# Sheet1.net
KiCad netlist of a schematic drawn in Altium Designer
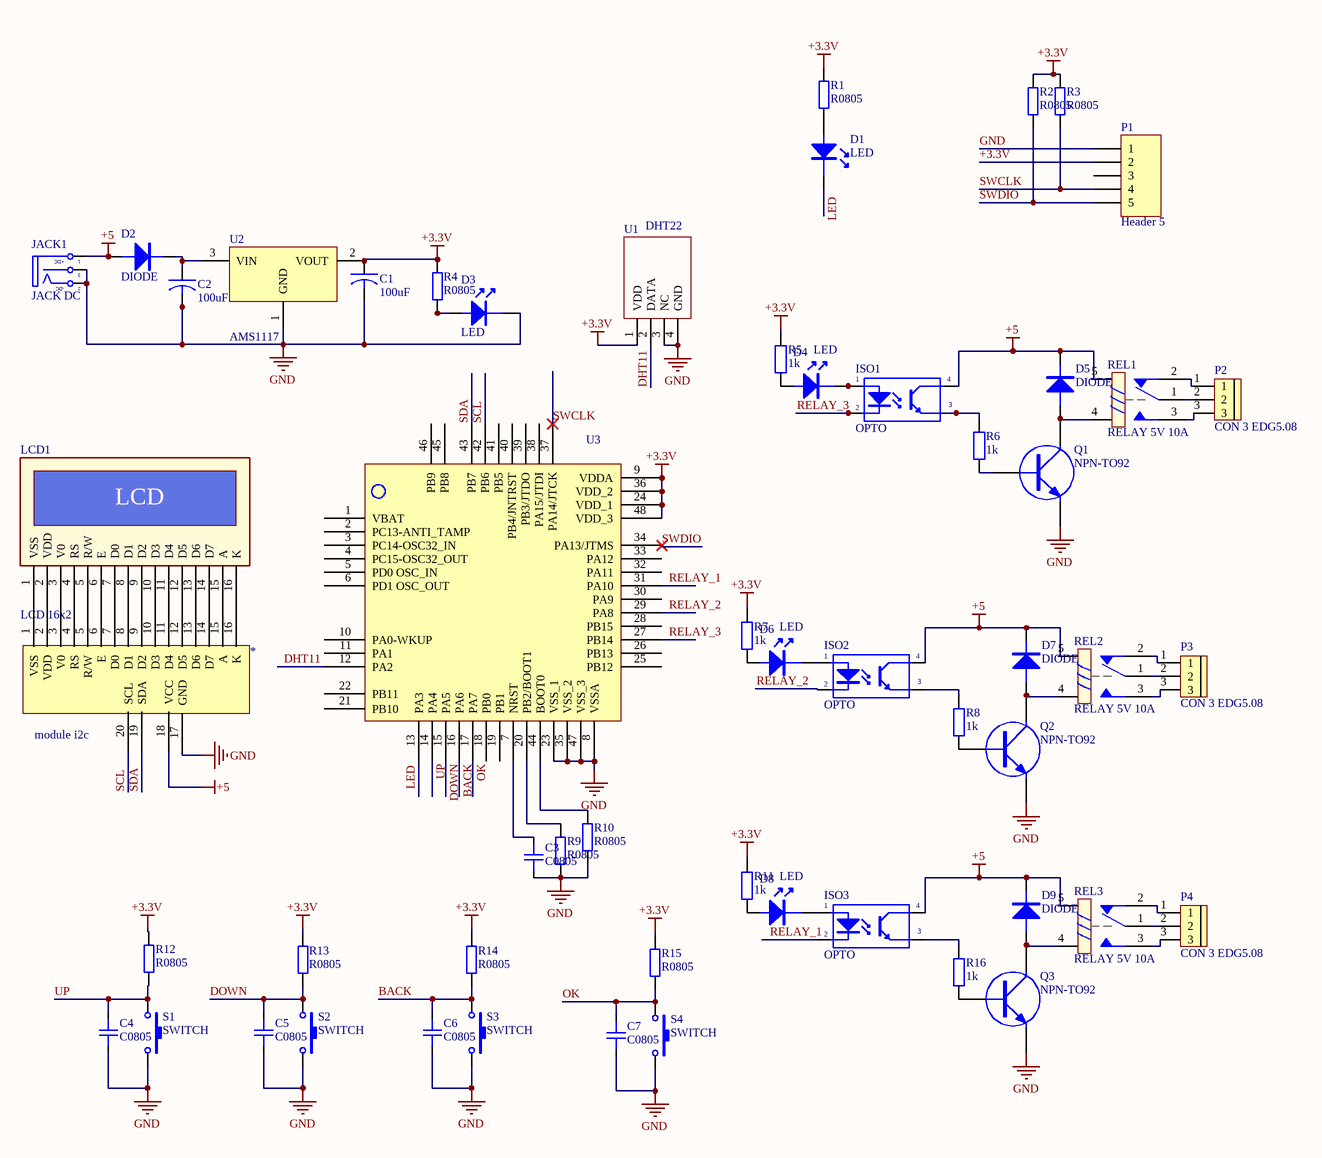
[diagram p0: Sheet1.SchDoc]

(export (version "E")
  (design (tool "Eeschema 10.0.6"))
  (components
    (comp (ref "*")
      (value "module i2c")
      (footprint "module_i2c")
      (libsource (lib "bethu") (part "module i2c"))
    )
    (comp (ref "C1") (value "100uF") (footprint "CAP_0805") (libsource (lib "bethu") (part "CAPACITOR")))
    (comp (ref "C2") (value "100uF") (footprint "CAP_0805") (libsource (lib "bethu") (part "CAPACITOR")))
    (comp (ref "C3")
      (value "C0805")
      (footprint "CAP_0805")
      (description "Capacitor SMD 0805")
      (libsource (lib "bethu") (part "CAP_0805"))
    )
    (comp (ref "C4")
      (value "C0805")
      (footprint "CAP_0805")
      (description "Capacitor SMD 0805")
      (libsource (lib "bethu") (part "CAP_0805"))
    )
    (comp (ref "C5")
      (value "C0805")
      (footprint "CAP_0805")
      (description "Capacitor SMD 0805")
      (libsource (lib "bethu") (part "CAP_0805"))
    )
    (comp (ref "C6")
      (value "C0805")
      (footprint "CAP_0805")
      (description "Capacitor SMD 0805")
      (libsource (lib "bethu") (part "CAP_0805"))
    )
    (comp (ref "C7")
      (value "C0805")
      (footprint "CAP_0805")
      (description "Capacitor SMD 0805")
      (libsource (lib "bethu") (part "CAP_0805"))
    )
    (comp (ref "D1") (value "LED") (footprint "LED5MM RED") (libsource (lib "bethu") (part "LED")))
    (comp (ref "D2") (value "DIODE") (footprint "DIODE SMA") (libsource (lib "bethu") (part "DIODE")))
    (comp (ref "D3") (value "LED") (footprint "LED5MM RED") (libsource (lib "bethu") (part "LED")))
    (comp (ref "D4") (value "LED") (footprint "LED5MM RED") (libsource (lib "bethu") (part "LED")))
    (comp (ref "D5") (value "DIODE") (footprint "DIODE DIP") (libsource (lib "bethu") (part "DIODE")))
    (comp (ref "D6") (value "LED") (footprint "LED5MM RED") (libsource (lib "bethu") (part "LED")))
    (comp (ref "D7") (value "DIODE") (footprint "DIODE DIP") (libsource (lib "bethu") (part "DIODE")))
    (comp (ref "D8") (value "LED") (footprint "LED5MM RED") (libsource (lib "bethu") (part "LED")))
    (comp (ref "D9") (value "DIODE") (footprint "DIODE DIP") (libsource (lib "bethu") (part "DIODE")))
    (comp (ref "ISO1") (value "OPTO") (footprint "PC817 DIP") (libsource (lib "bethu") (part "OPTO")))
    (comp (ref "ISO2") (value "OPTO") (footprint "PC817 DIP") (libsource (lib "bethu") (part "OPTO")))
    (comp (ref "ISO3") (value "OPTO") (footprint "PC817 DIP") (libsource (lib "bethu") (part "OPTO")))
    (comp (ref "JACK1") (value "JACK DC") (footprint "JACK DC") (libsource (lib "bethu") (part "JACK DC")))
    (comp (ref "LCD1")
      (value "LCD 16x2")
      (footprint "LCD 16x2-A")
      (libsource (lib "bethu") (part "LCD 16x2"))
    )
    (comp (ref "P1")
      (value "Header 5")
      (footprint "JP 1X5 DT")
      (fields (field (name "PUBLISHER") "Altium Limited"))
      (libsource (lib "bethu") (part "Header 5"))
    )
    (comp (ref "P2")
      (value "CON 3 EDG5.08")
      (footprint "Con 3 KF301 5.08")
      (description "Cắm")
      (libsource (lib "bethu") (part "CON 3 EDG5.08"))
    )
    (comp (ref "P3")
      (value "CON 3 EDG5.08")
      (footprint "Con 3 KF301 5.08")
      (description "Cắm")
      (libsource (lib "bethu") (part "CON 3 EDG5.08"))
    )
    (comp (ref "P4")
      (value "CON 3 EDG5.08")
      (footprint "Con 3 KF301 5.08")
      (description "Cắm")
      (libsource (lib "bethu") (part "CON 3 EDG5.08"))
    )
    (comp (ref "Q1") (value "NPN-TO92") (footprint "TO-92") (libsource (lib "bethu") (part "NPN-TO92")))
    (comp (ref "Q2") (value "NPN-TO92") (footprint "TO-92") (libsource (lib "bethu") (part "NPN-TO92")))
    (comp (ref "Q3") (value "NPN-TO92") (footprint "TO-92") (libsource (lib "bethu") (part "NPN-TO92")))
    (comp (ref "R1")
      (value "R0805")
      (footprint "RES_0805")
      (description "Resistor SMD 0805")
      (libsource (lib "bethu") (part "RES_0805"))
    )
    (comp (ref "R2")
      (value "R0805")
      (footprint "RES_0805")
      (description "Resistor SMD 0805")
      (libsource (lib "bethu") (part "RES_0805"))
    )
    (comp (ref "R3")
      (value "R0805")
      (footprint "RES_0805")
      (description "Resistor SMD 0805")
      (libsource (lib "bethu") (part "RES_0805"))
    )
    (comp (ref "R4")
      (value "R0805")
      (footprint "RES_0805")
      (description "Resistor SMD 0805")
      (libsource (lib "bethu") (part "RES_0805"))
    )
    (comp (ref "R5") (value "1k") (footprint "RESISTOR") (libsource (lib "bethu") (part "RESISTOR")))
    (comp (ref "R6") (value "1k") (footprint "RESISTOR") (libsource (lib "bethu") (part "RESISTOR")))
    (comp (ref "R7") (value "1k") (footprint "RESISTOR") (libsource (lib "bethu") (part "RESISTOR")))
    (comp (ref "R8") (value "1k") (footprint "RESISTOR") (libsource (lib "bethu") (part "RESISTOR")))
    (comp (ref "R9")
      (value "R0805")
      (footprint "RES_0805")
      (description "Resistor SMD 0805")
      (libsource (lib "bethu") (part "RES_0805"))
    )
    (comp (ref "R10")
      (value "R0805")
      (footprint "RES_0805")
      (description "Resistor SMD 0805")
      (libsource (lib "bethu") (part "RES_0805"))
    )
    (comp (ref "R11") (value "1k") (footprint "RESISTOR") (libsource (lib "bethu") (part "RESISTOR")))
    (comp (ref "R12")
      (value "R0805")
      (footprint "RES_0805")
      (description "Resistor SMD 0805")
      (libsource (lib "bethu") (part "RES_0805"))
    )
    (comp (ref "R13")
      (value "R0805")
      (footprint "RES_0805")
      (description "Resistor SMD 0805")
      (libsource (lib "bethu") (part "RES_0805"))
    )
    (comp (ref "R14")
      (value "R0805")
      (footprint "RES_0805")
      (description "Resistor SMD 0805")
      (libsource (lib "bethu") (part "RES_0805"))
    )
    (comp (ref "R15")
      (value "R0805")
      (footprint "RES_0805")
      (description "Resistor SMD 0805")
      (libsource (lib "bethu") (part "RES_0805"))
    )
    (comp (ref "R16") (value "1k") (footprint "RESISTOR") (libsource (lib "bethu") (part "RESISTOR")))
    (comp (ref "REL1")
      (value "RELAY 5V 10A")
      (footprint "RELAY 5V-10A")
      (libsource (lib "bethu") (part "RELAY 5V 10A"))
    )
    (comp (ref "REL2")
      (value "RELAY 5V 10A")
      (footprint "RELAY 5V-10A")
      (libsource (lib "bethu") (part "RELAY 5V 10A"))
    )
    (comp (ref "REL3")
      (value "RELAY 5V 10A")
      (footprint "RELAY 5V-10A")
      (libsource (lib "bethu") (part "RELAY 5V 10A"))
    )
    (comp (ref "S1")
      (value "SWITCH")
      (footprint "SW 4PIN 12x12x7")
      (fields (field (name "PUBLISHER") "Altium Limited"))
      (libsource (lib "bethu") (part "SWITCH"))
    )
    (comp (ref "S2")
      (value "SWITCH")
      (footprint "SW 4PIN 12x12x7")
      (fields (field (name "PUBLISHER") "Altium Limited"))
      (libsource (lib "bethu") (part "SWITCH"))
    )
    (comp (ref "S3")
      (value "SWITCH")
      (footprint "SW 4PIN 12x12x7")
      (fields (field (name "PUBLISHER") "Altium Limited"))
      (libsource (lib "bethu") (part "SWITCH"))
    )
    (comp (ref "S4")
      (value "SWITCH")
      (footprint "SW 4PIN 12x12x7")
      (fields (field (name "PUBLISHER") "Altium Limited"))
      (libsource (lib "bethu") (part "SWITCH"))
    )
    (comp (ref "U1") (value "DHT22") (footprint "DHT22") (libsource (lib "bethu") (part "DHT22")))
    (comp (ref "U2")
      (value "AMS1117")
      (footprint "SOT223 - 3 LEAD")
      (libsource (lib "bethu") (part "AMS1117"))
    )
    (comp (ref "U3")
      (value "STM32F103C8T6-LQFP48")
      (footprint "LQFP 48 PIN")
      (fields (field (name "PUBLISHER") "Altium Limited"))
      (libsource (lib "bethu") (part "STM32F103C8T6-LQFP48"))
    )
  )
  (nets
    (net (code "1") (name "+3.3V") (class "Default")
      (node (ref "C1") (pin "1") (pinfunction "1_1") (pintype "passive"))
      (node (ref "P1") (pin "2") (pinfunction "2_2") (pintype "passive"))
      (node (ref "R1") (pin "1") (pinfunction "1_1") (pintype "passive"))
      (node (ref "R11") (pin "2") (pinfunction "2_2") (pintype "passive"))
      (node (ref "R12") (pin "2") (pinfunction "2_2") (pintype "passive"))
      (node (ref "R13") (pin "2") (pinfunction "2_2") (pintype "passive"))
      (node (ref "R14") (pin "2") (pinfunction "2_2") (pintype "passive"))
      (node (ref "R15") (pin "2") (pinfunction "2_2") (pintype "passive"))
      (node (ref "R2") (pin "1") (pinfunction "1_1") (pintype "passive"))
      (node (ref "R3") (pin "1") (pinfunction "1_1") (pintype "passive"))
      (node (ref "R4") (pin "1") (pinfunction "1_1") (pintype "passive"))
      (node (ref "R5") (pin "2") (pinfunction "2_2") (pintype "passive"))
      (node (ref "R7") (pin "2") (pinfunction "2_2") (pintype "passive"))
      (node (ref "U1") (pin "1") (pinfunction "VDD_1") (pintype "passive"))
      (node (ref "U2") (pin "2") (pinfunction "VOUT_2") (pintype "passive"))
      (node (ref "U3") (pin "24") (pinfunction "VDD_1_24") (pintype "passive"))
      (node (ref "U3") (pin "36") (pinfunction "VDD_2_36") (pintype "passive"))
      (node (ref "U3") (pin "48") (pinfunction "VDD_3_48") (pintype "passive"))
      (node (ref "U3") (pin "9") (pinfunction "VDDA_9") (pintype "passive"))
    )
    (net (code "2") (name "+5") (class "Default")
      (node (ref "*") (pin "18") (pinfunction "VCC_18") (pintype "passive"))
      (node (ref "D2") (pin "1") (pinfunction "1_1") (pintype "passive"))
      (node (ref "D5") (pin "2") (pinfunction "2_2") (pintype "passive"))
      (node (ref "D7") (pin "2") (pinfunction "2_2") (pintype "passive"))
      (node (ref "D9") (pin "2") (pinfunction "2_2") (pintype "passive"))
      (node (ref "ISO1") (pin "4") (pinfunction "C_4") (pintype "passive"))
      (node (ref "ISO2") (pin "4") (pinfunction "C_4") (pintype "passive"))
      (node (ref "ISO3") (pin "4") (pinfunction "C_4") (pintype "passive"))
      (node (ref "JACK1") (pin "1") (pinfunction "T_1") (pintype "passive"))
      (node (ref "REL1") (pin "5") (pinfunction "5_5") (pintype "passive"))
      (node (ref "REL2") (pin "5") (pinfunction "5_5") (pintype "passive"))
      (node (ref "REL3") (pin "5") (pinfunction "5_5") (pintype "passive"))
    )
    (net (code "3") (name "/BACK") (class "Default")
      (node (ref "C6") (pin "1") (pinfunction "1_1") (pintype "passive"))
      (node (ref "R14") (pin "1") (pinfunction "1_1") (pintype "passive"))
      (node (ref "S3") (pin "1") (pinfunction "1_1") (pintype "passive"))
      (node (ref "U3") (pin "16") (pinfunction "PA6_16") (pintype "passive"))
    )
    (net (code "4") (name "/DHT11") (class "Default")
      (node (ref "U1") (pin "2") (pinfunction "DATA_2") (pintype "passive"))
      (node (ref "U3") (pin "12") (pinfunction "PA2_12") (pintype "passive"))
    )
    (net (code "5") (name "/DOWN") (class "Default")
      (node (ref "C5") (pin "1") (pinfunction "1_1") (pintype "passive"))
      (node (ref "R13") (pin "1") (pinfunction "1_1") (pintype "passive"))
      (node (ref "S2") (pin "1") (pinfunction "1_1") (pintype "passive"))
      (node (ref "U3") (pin "15") (pinfunction "PA5_15") (pintype "passive"))
    )
    (net (code "6") (name "/LED") (class "Default")
      (node (ref "D1") (pin "2") (pinfunction "2_2") (pintype "passive"))
      (node (ref "U3") (pin "13") (pinfunction "PA3_13") (pintype "passive"))
    )
    (net (code "7") (name "/OK") (class "Default")
      (node (ref "C7") (pin "1") (pinfunction "1_1") (pintype "passive"))
      (node (ref "R15") (pin "1") (pinfunction "1_1") (pintype "passive"))
      (node (ref "S4") (pin "1") (pinfunction "1_1") (pintype "passive"))
      (node (ref "U3") (pin "17") (pinfunction "PA7_17") (pintype "passive"))
    )
    (net (code "8") (name "/RELAY_1") (class "Default")
      (node (ref "ISO3") (pin "2") (pinfunction "K_2") (pintype "passive"))
      (node (ref "U3") (pin "31") (pinfunction "PA10_31") (pintype "passive"))
    )
    (net (code "9") (name "/RELAY_2") (class "Default")
      (node (ref "ISO2") (pin "2") (pinfunction "K_2") (pintype "passive"))
      (node (ref "U3") (pin "29") (pinfunction "PA8_29") (pintype "passive"))
    )
    (net (code "10") (name "/RELAY_3") (class "Default")
      (node (ref "ISO1") (pin "2") (pinfunction "K_2") (pintype "passive"))
      (node (ref "U3") (pin "27") (pinfunction "PB14_27") (pintype "passive"))
    )
    (net (code "11") (name "/SCL") (class "Default")
      (node (ref "*") (pin "20") (pinfunction "SCL_20") (pintype "passive"))
      (node (ref "U3") (pin "42") (pinfunction "PB6_42") (pintype "passive"))
    )
    (net (code "12") (name "/SDA") (class "Default")
      (node (ref "*") (pin "19") (pinfunction "SDA_19") (pintype "passive"))
      (node (ref "U3") (pin "43") (pinfunction "PB7_43") (pintype "passive"))
    )
    (net (code "13") (name "/SWCLK") (class "Default")
      (node (ref "P1") (pin "4") (pinfunction "4_4") (pintype "passive"))
      (node (ref "R3") (pin "2") (pinfunction "2_2") (pintype "passive"))
      (node (ref "U3") (pin "37") (pinfunction "PA14/JTCK_37") (pintype "passive"))
    )
    (net (code "14") (name "/SWDIO") (class "Default")
      (node (ref "P1") (pin "5") (pinfunction "5_5") (pintype "passive"))
      (node (ref "R2") (pin "2") (pinfunction "2_2") (pintype "passive"))
      (node (ref "U3") (pin "34") (pinfunction "PA13/JTMS_34") (pintype "passive"))
    )
    (net (code "15") (name "/UP") (class "Default")
      (node (ref "C4") (pin "1") (pinfunction "1_1") (pintype "passive"))
      (node (ref "R12") (pin "1") (pinfunction "1_1") (pintype "passive"))
      (node (ref "S1") (pin "1") (pinfunction "1_1") (pintype "passive"))
      (node (ref "U3") (pin "14") (pinfunction "PA4_14") (pintype "passive"))
    )
    (net (code "16") (name "GND") (class "Default")
      (node (ref "*") (pin "17") (pinfunction "GND_17") (pintype "passive"))
      (node (ref "C1") (pin "2") (pinfunction "2_2") (pintype "passive"))
      (node (ref "C2") (pin "2") (pinfunction "2_2") (pintype "passive"))
      (node (ref "C3") (pin "1") (pinfunction "1_1") (pintype "passive"))
      (node (ref "C4") (pin "2") (pinfunction "2_2") (pintype "passive"))
      (node (ref "C5") (pin "2") (pinfunction "2_2") (pintype "passive"))
      (node (ref "C6") (pin "2") (pinfunction "2_2") (pintype "passive"))
      (node (ref "C7") (pin "2") (pinfunction "2_2") (pintype "passive"))
      (node (ref "D3") (pin "2") (pinfunction "2_2") (pintype "passive"))
      (node (ref "JACK1") (pin "2") (pinfunction "TN_2") (pintype "passive"))
      (node (ref "JACK1") (pin "3") (pinfunction "S_3") (pintype "power_in"))
      (node (ref "P1") (pin "1") (pinfunction "1_1") (pintype "passive"))
      (node (ref "Q1") (pin "1") (pinfunction "E_1") (pintype "passive"))
      (node (ref "Q2") (pin "1") (pinfunction "E_1") (pintype "passive"))
      (node (ref "Q3") (pin "1") (pinfunction "E_1") (pintype "passive"))
      (node (ref "R10") (pin "1") (pinfunction "1_1") (pintype "passive"))
      (node (ref "R9") (pin "1") (pinfunction "1_1") (pintype "passive"))
      (node (ref "S1") (pin "2") (pinfunction "2_2") (pintype "passive"))
      (node (ref "S2") (pin "2") (pinfunction "2_2") (pintype "passive"))
      (node (ref "S3") (pin "2") (pinfunction "2_2") (pintype "passive"))
      (node (ref "S4") (pin "2") (pinfunction "2_2") (pintype "passive"))
      (node (ref "U1") (pin "3") (pinfunction "NC_3") (pintype "passive"))
      (node (ref "U1") (pin "4") (pinfunction "GND_4") (pintype "passive"))
      (node (ref "U2") (pin "1") (pinfunction "GND_1") (pintype "passive"))
      (node (ref "U3") (pin "23") (pinfunction "VSS_1_23") (pintype "passive"))
      (node (ref "U3") (pin "35") (pinfunction "VSS_2_35") (pintype "passive"))
      (node (ref "U3") (pin "47") (pinfunction "VSS_3_47") (pintype "passive"))
      (node (ref "U3") (pin "8") (pinfunction "VSSA_8") (pintype "passive"))
    )
    (net (code "17") (name "Net-(*-A)") (class "Default")
      (node (ref "*") (pin "15") (pinfunction "A_15") (pintype "passive"))
      (node (ref "LCD1") (pin "15") (pinfunction "A_15") (pintype "passive"))
    )
    (net (code "18") (name "Net-(*-D0)") (class "Default")
      (node (ref "*") (pin "7") (pinfunction "D0_7") (pintype "passive"))
      (node (ref "LCD1") (pin "7") (pinfunction "D0_7") (pintype "passive"))
    )
    (net (code "19") (name "Net-(*-D1)") (class "Default")
      (node (ref "*") (pin "8") (pinfunction "D1_8") (pintype "passive"))
      (node (ref "LCD1") (pin "8") (pinfunction "D1_8") (pintype "passive"))
    )
    (net (code "20") (name "Net-(*-D2)") (class "Default")
      (node (ref "*") (pin "9") (pinfunction "D2_9") (pintype "passive"))
      (node (ref "LCD1") (pin "9") (pinfunction "D2_9") (pintype "passive"))
    )
    (net (code "21") (name "Net-(*-D3)") (class "Default")
      (node (ref "*") (pin "10") (pinfunction "D3_10") (pintype "passive"))
      (node (ref "LCD1") (pin "10") (pinfunction "D3_10") (pintype "passive"))
    )
    (net (code "22") (name "Net-(*-D4)") (class "Default")
      (node (ref "*") (pin "11") (pinfunction "D4_11") (pintype "passive"))
      (node (ref "LCD1") (pin "11") (pinfunction "D4_11") (pintype "passive"))
    )
    (net (code "23") (name "Net-(*-D5)") (class "Default")
      (node (ref "*") (pin "12") (pinfunction "D5_12") (pintype "passive"))
      (node (ref "LCD1") (pin "12") (pinfunction "D5_12") (pintype "passive"))
    )
    (net (code "24") (name "Net-(*-D6)") (class "Default")
      (node (ref "*") (pin "13") (pinfunction "D6_13") (pintype "passive"))
      (node (ref "LCD1") (pin "13") (pinfunction "D6_13") (pintype "passive"))
    )
    (net (code "25") (name "Net-(*-D7)") (class "Default")
      (node (ref "*") (pin "14") (pinfunction "D7_14") (pintype "passive"))
      (node (ref "LCD1") (pin "14") (pinfunction "D7_14") (pintype "passive"))
    )
    (net (code "26") (name "Net-(*-E)") (class "Default")
      (node (ref "*") (pin "6") (pinfunction "E_6") (pintype "passive"))
      (node (ref "LCD1") (pin "6") (pinfunction "E_6") (pintype "passive"))
    )
    (net (code "27") (name "Net-(*-K)") (class "Default")
      (node (ref "*") (pin "16") (pinfunction "K_16") (pintype "passive"))
      (node (ref "LCD1") (pin "16") (pinfunction "K_16") (pintype "passive"))
    )
    (net (code "28") (name "Net-(*-RS)") (class "Default")
      (node (ref "*") (pin "4") (pinfunction "RS_4") (pintype "passive"))
      (node (ref "LCD1") (pin "4") (pinfunction "RS_4") (pintype "passive"))
    )
    (net (code "29") (name "Net-(*-R{slash}W)") (class "Default")
      (node (ref "*") (pin "5") (pinfunction "R/W_5") (pintype "passive"))
      (node (ref "LCD1") (pin "5") (pinfunction "R/W_5") (pintype "passive"))
    )
    (net (code "30") (name "Net-(*-V0)") (class "Default")
      (node (ref "*") (pin "3") (pinfunction "V0_3") (pintype "passive"))
      (node (ref "LCD1") (pin "3") (pinfunction "V0_3") (pintype "passive"))
    )
    (net (code "31") (name "Net-(*-VDD)") (class "Default")
      (node (ref "*") (pin "2") (pinfunction "VDD_2") (pintype "passive"))
      (node (ref "LCD1") (pin "2") (pinfunction "VDD_2") (pintype "passive"))
    )
    (net (code "32") (name "Net-(*-VSS)") (class "Default")
      (node (ref "*") (pin "1") (pinfunction "VSS_1") (pintype "passive"))
      (node (ref "LCD1") (pin "1") (pinfunction "VSS_1") (pintype "passive"))
    )
    (net (code "33") (name "Net-(D1-Pad1)") (class "Default")
      (node (ref "D1") (pin "1") (pinfunction "1_1") (pintype "passive"))
      (node (ref "R1") (pin "2") (pinfunction "2_2") (pintype "passive"))
    )
    (net (code "34") (name "Net-(D3-Pad1)") (class "Default")
      (node (ref "D3") (pin "1") (pinfunction "1_1") (pintype "passive"))
      (node (ref "R4") (pin "2") (pinfunction "2_2") (pintype "passive"))
    )
    (net (code "35") (name "Net-(D4-Pad1)") (class "Default")
      (node (ref "D4") (pin "1") (pinfunction "1_1") (pintype "passive"))
      (node (ref "R5") (pin "1") (pinfunction "1_1") (pintype "passive"))
    )
    (net (code "36") (name "Net-(D6-Pad1)") (class "Default")
      (node (ref "D6") (pin "1") (pinfunction "1_1") (pintype "passive"))
      (node (ref "R7") (pin "1") (pinfunction "1_1") (pintype "passive"))
    )
    (net (code "37") (name "Net-(D8-Pad1)") (class "Default")
      (node (ref "D8") (pin "1") (pinfunction "1_1") (pintype "passive"))
      (node (ref "R11") (pin "1") (pinfunction "1_1") (pintype "passive"))
    )
    (net (code "38") (name "Net-(ISO1-A)") (class "Default")
      (node (ref "D4") (pin "2") (pinfunction "2_2") (pintype "passive"))
      (node (ref "ISO1") (pin "1") (pinfunction "A_1") (pintype "passive"))
    )
    (net (code "39") (name "Net-(ISO1-E)") (class "Default")
      (node (ref "ISO1") (pin "3") (pinfunction "E_3") (pintype "passive"))
      (node (ref "R6") (pin "1") (pinfunction "1_1") (pintype "passive"))
    )
    (net (code "40") (name "Net-(ISO2-A)") (class "Default")
      (node (ref "D6") (pin "2") (pinfunction "2_2") (pintype "passive"))
      (node (ref "ISO2") (pin "1") (pinfunction "A_1") (pintype "passive"))
    )
    (net (code "41") (name "Net-(ISO2-E)") (class "Default")
      (node (ref "ISO2") (pin "3") (pinfunction "E_3") (pintype "passive"))
      (node (ref "R8") (pin "1") (pinfunction "1_1") (pintype "passive"))
    )
    (net (code "42") (name "Net-(ISO3-A)") (class "Default")
      (node (ref "D8") (pin "2") (pinfunction "2_2") (pintype "passive"))
      (node (ref "ISO3") (pin "1") (pinfunction "A_1") (pintype "passive"))
    )
    (net (code "43") (name "Net-(ISO3-E)") (class "Default")
      (node (ref "ISO3") (pin "3") (pinfunction "E_3") (pintype "passive"))
      (node (ref "R16") (pin "1") (pinfunction "1_1") (pintype "passive"))
    )
    (net (code "44") (name "Net-(P2-Pad1)") (class "Default")
      (node (ref "P2") (pin "1") (pinfunction "1_1") (pintype "passive"))
      (node (ref "REL1") (pin "2") (pinfunction "2_2") (pintype "passive"))
    )
    (net (code "45") (name "Net-(P2-Pad2)") (class "Default")
      (node (ref "P2") (pin "2") (pinfunction "2_2") (pintype "passive"))
      (node (ref "REL1") (pin "1") (pinfunction "1_1") (pintype "passive"))
    )
    (net (code "46") (name "Net-(P2-Pad3)") (class "Default")
      (node (ref "P2") (pin "3") (pinfunction "3_3") (pintype "passive"))
      (node (ref "REL1") (pin "3") (pinfunction "3_3") (pintype "passive"))
    )
    (net (code "47") (name "Net-(P3-Pad1)") (class "Default")
      (node (ref "P3") (pin "1") (pinfunction "1_1") (pintype "passive"))
      (node (ref "REL2") (pin "2") (pinfunction "2_2") (pintype "passive"))
    )
    (net (code "48") (name "Net-(P3-Pad2)") (class "Default")
      (node (ref "P3") (pin "2") (pinfunction "2_2") (pintype "passive"))
      (node (ref "REL2") (pin "1") (pinfunction "1_1") (pintype "passive"))
    )
    (net (code "49") (name "Net-(P3-Pad3)") (class "Default")
      (node (ref "P3") (pin "3") (pinfunction "3_3") (pintype "passive"))
      (node (ref "REL2") (pin "3") (pinfunction "3_3") (pintype "passive"))
    )
    (net (code "50") (name "Net-(P4-Pad1)") (class "Default")
      (node (ref "P4") (pin "1") (pinfunction "1_1") (pintype "passive"))
      (node (ref "REL3") (pin "2") (pinfunction "2_2") (pintype "passive"))
    )
    (net (code "51") (name "Net-(P4-Pad2)") (class "Default")
      (node (ref "P4") (pin "2") (pinfunction "2_2") (pintype "passive"))
      (node (ref "REL3") (pin "1") (pinfunction "1_1") (pintype "passive"))
    )
    (net (code "52") (name "Net-(P4-Pad3)") (class "Default")
      (node (ref "P4") (pin "3") (pinfunction "3_3") (pintype "passive"))
      (node (ref "REL3") (pin "3") (pinfunction "3_3") (pintype "passive"))
    )
    (net (code "53") (name "Net-(Q1-B)") (class "Default")
      (node (ref "Q1") (pin "3") (pinfunction "B_3") (pintype "passive"))
      (node (ref "R6") (pin "2") (pinfunction "2_2") (pintype "passive"))
    )
    (net (code "54") (name "Net-(Q1-C)") (class "Default")
      (node (ref "D5") (pin "1") (pinfunction "1_1") (pintype "passive"))
      (node (ref "Q1") (pin "2") (pinfunction "C_2") (pintype "passive"))
      (node (ref "REL1") (pin "4") (pinfunction "4_4") (pintype "passive"))
    )
    (net (code "55") (name "Net-(Q2-B)") (class "Default")
      (node (ref "Q2") (pin "3") (pinfunction "B_3") (pintype "passive"))
      (node (ref "R8") (pin "2") (pinfunction "2_2") (pintype "passive"))
    )
    (net (code "56") (name "Net-(Q2-C)") (class "Default")
      (node (ref "D7") (pin "1") (pinfunction "1_1") (pintype "passive"))
      (node (ref "Q2") (pin "2") (pinfunction "C_2") (pintype "passive"))
      (node (ref "REL2") (pin "4") (pinfunction "4_4") (pintype "passive"))
    )
    (net (code "57") (name "Net-(Q3-B)") (class "Default")
      (node (ref "Q3") (pin "3") (pinfunction "B_3") (pintype "passive"))
      (node (ref "R16") (pin "2") (pinfunction "2_2") (pintype "passive"))
    )
    (net (code "58") (name "Net-(Q3-C)") (class "Default")
      (node (ref "D9") (pin "1") (pinfunction "1_1") (pintype "passive"))
      (node (ref "Q3") (pin "2") (pinfunction "C_2") (pintype "passive"))
      (node (ref "REL3") (pin "4") (pinfunction "4_4") (pintype "passive"))
    )
    (net (code "59") (name "Net-(U2-VIN)") (class "Default")
      (node (ref "C2") (pin "1") (pinfunction "1_1") (pintype "passive"))
      (node (ref "D2") (pin "2") (pinfunction "2_2") (pintype "passive"))
      (node (ref "U2") (pin "3") (pinfunction "VIN_3") (pintype "passive"))
    )
    (net (code "60") (name "Net-(U3-BOOT0)") (class "Default")
      (node (ref "R10") (pin "2") (pinfunction "2_2") (pintype "passive"))
      (node (ref "U3") (pin "44") (pinfunction "BOOT0_44") (pintype "passive"))
    )
    (net (code "61") (name "Net-(U3-NRST)") (class "Default")
      (node (ref "C3") (pin "2") (pinfunction "2_2") (pintype "passive"))
      (node (ref "U3") (pin "7") (pinfunction "NRST_7") (pintype "passive"))
    )
    (net (code "62") (name "Net-(U3-PB2{slash}BOOT1)") (class "Default")
      (node (ref "R9") (pin "2") (pinfunction "2_2") (pintype "passive"))
      (node (ref "U3") (pin "20") (pinfunction "PB2/BOOT1_20") (pintype "passive"))
    )
    (net (code "63") (name "unconnected-(P1-Pad3)") (class "Default")
      (node (ref "P1") (pin "3") (pinfunction "3_3") (pintype "passive"))
    )
    (net (code "64") (name "unconnected-(U3-PA0-WKUP-Pad10)") (class "Default")
      (node (ref "U3") (pin "10") (pinfunction "PA0-WKUP_10") (pintype "passive"))
    )
    (net (code "65") (name "unconnected-(U3-PA1-Pad11)") (class "Default")
      (node (ref "U3") (pin "11") (pinfunction "PA1_11") (pintype "passive"))
    )
    (net (code "66") (name "unconnected-(U3-PA9-Pad30)") (class "Default")
      (node (ref "U3") (pin "30") (pinfunction "PA9_30") (pintype "passive"))
    )
    (net (code "67") (name "unconnected-(U3-PA11-Pad32)") (class "Default")
      (node (ref "U3") (pin "32") (pinfunction "PA11_32") (pintype "passive"))
    )
    (net (code "68") (name "unconnected-(U3-PA12-Pad33)") (class "Default")
      (node (ref "U3") (pin "33") (pinfunction "PA12_33") (pintype "passive"))
    )
    (net (code "69") (name "unconnected-(U3-PA15{slash}JTDI-Pad38)") (class "Default")
      (node (ref "U3") (pin "38") (pinfunction "PA15/JTDI_38") (pintype "passive"))
    )
    (net (code "70") (name "unconnected-(U3-PB0-Pad18)") (class "Default")
      (node (ref "U3") (pin "18") (pinfunction "PB0_18") (pintype "passive"))
    )
    (net (code "71") (name "unconnected-(U3-PB1-Pad19)") (class "Default")
      (node (ref "U3") (pin "19") (pinfunction "PB1_19") (pintype "passive"))
    )
    (net (code "72") (name "unconnected-(U3-PB3{slash}JTDO-Pad39)") (class "Default")
      (node (ref "U3") (pin "39") (pinfunction "PB3/JTDO_39") (pintype "passive"))
    )
    (net (code "73") (name "unconnected-(U3-PB4{slash}JNTRST-Pad40)") (class "Default")
      (node (ref "U3") (pin "40") (pinfunction "PB4/JNTRST_40") (pintype "passive"))
    )
    (net (code "74") (name "unconnected-(U3-PB5-Pad41)") (class "Default")
      (node (ref "U3") (pin "41") (pinfunction "PB5_41") (pintype "passive"))
    )
    (net (code "75") (name "unconnected-(U3-PB8-Pad45)") (class "Default")
      (node (ref "U3") (pin "45") (pinfunction "PB8_45") (pintype "passive"))
    )
    (net (code "76") (name "unconnected-(U3-PB9-Pad46)") (class "Default")
      (node (ref "U3") (pin "46") (pinfunction "PB9_46") (pintype "passive"))
    )
    (net (code "77") (name "unconnected-(U3-PB10-Pad21)") (class "Default")
      (node (ref "U3") (pin "21") (pinfunction "PB10_21") (pintype "passive"))
    )
    (net (code "78") (name "unconnected-(U3-PB11-Pad22)") (class "Default")
      (node (ref "U3") (pin "22") (pinfunction "PB11_22") (pintype "passive"))
    )
    (net (code "79") (name "unconnected-(U3-PB12-Pad25)") (class "Default")
      (node (ref "U3") (pin "25") (pinfunction "PB12_25") (pintype "passive"))
    )
    (net (code "80") (name "unconnected-(U3-PB13-Pad26)") (class "Default")
      (node (ref "U3") (pin "26") (pinfunction "PB13_26") (pintype "passive"))
    )
    (net (code "81") (name "unconnected-(U3-PB15-Pad28)") (class "Default")
      (node (ref "U3") (pin "28") (pinfunction "PB15_28") (pintype "passive"))
    )
    (net (code "82") (name "unconnected-(U3-PC13-ANTI_TAMP-Pad2)") (class "Default")
      (node (ref "U3") (pin "2") (pinfunction "PC13-ANTI_TAMP_2") (pintype "passive"))
    )
    (net (code "83") (name "unconnected-(U3-PC14-OSC32_IN-Pad3)") (class "Default")
      (node (ref "U3") (pin "3") (pinfunction "PC14-OSC32_IN_3") (pintype "passive"))
    )
    (net (code "84") (name "unconnected-(U3-PC15-OSC32_OUT-Pad4)") (class "Default")
      (node (ref "U3") (pin "4") (pinfunction "PC15-OSC32_OUT_4") (pintype "passive"))
    )
    (net (code "85") (name "unconnected-(U3-PD0_OSC_IN-Pad5)") (class "Default")
      (node (ref "U3") (pin "5") (pinfunction "PD0_OSC_IN_5") (pintype "passive"))
    )
    (net (code "86") (name "unconnected-(U3-PD1_OSC_OUT-Pad6)") (class "Default")
      (node (ref "U3") (pin "6") (pinfunction "PD1_OSC_OUT_6") (pintype "passive"))
    )
    (net (code "87") (name "unconnected-(U3-VBAT-Pad1)") (class "Default")
      (node (ref "U3") (pin "1") (pinfunction "VBAT_1") (pintype "passive"))
    )
  )
)
